# PMOD_STMod_connector.net
KiCad netlist of a schematic drawn in Altium Designer
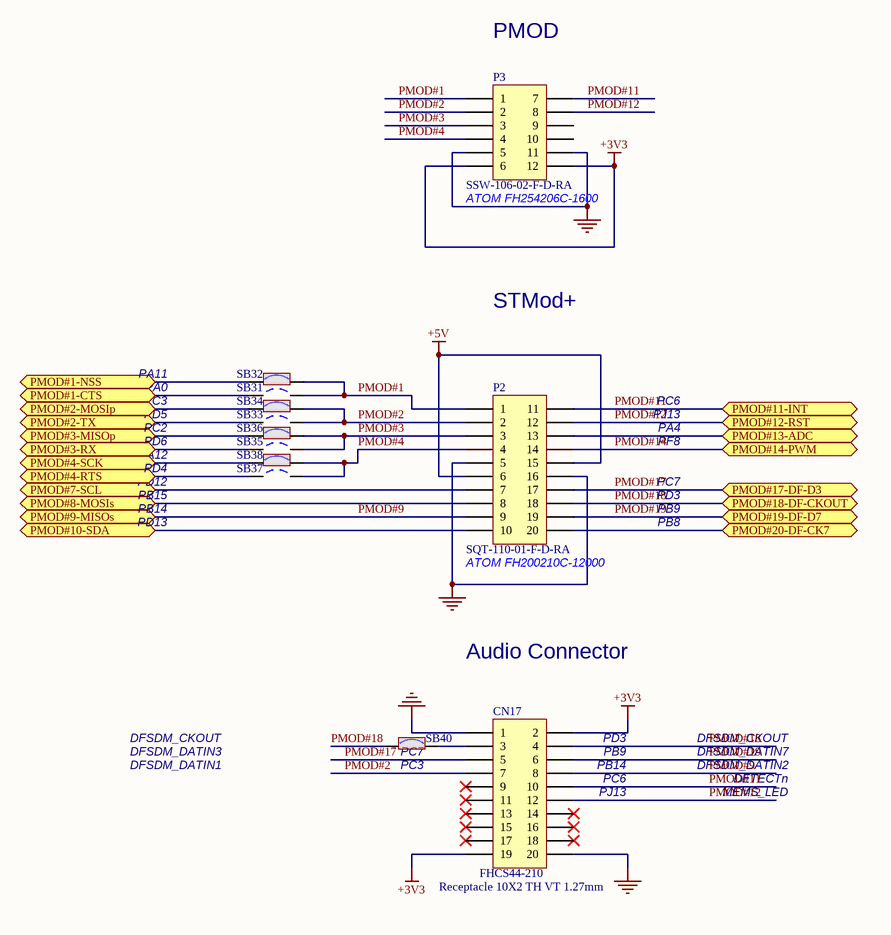
[diagram p0: PMOD_STMod+ connector .SchDoc]

(export (version "E")
  (design (tool "Eeschema 10.0.6"))
  (components
    (comp (ref "CN17")
      (value "Receptacle 10X2 TH VT 1.27mm")
      (footprint "MODULE_20TH_48X29")
      (description "20 Position Receptacle Connector 0.050\" (1.27mm) Through Hole Vertical Mount")
      (fields (field (name "ORDER_CODE") "FHCS44-210"))
      (libsource (lib "MCD_TEMP_PCH") (part "Receptacle 10X2 TH VT 1.27mm"))
    )
    (comp (ref "P2")
      (value "SQT-110-01-F-D-RA")
      (footprint "SQT-110-01-F-D-RA")
      (description "Header, 10-Pin, Dual row")
      (fields (field (name "PUBLISHER") "Altium Limited"))
      (libsource (lib "Miscellaneous Connectors") (part "Header 10X2A"))
    )
    (comp (ref "P3")
      (value "SSW-106-02-F-D-RA")
      (footprint "SSW-106-02-F-D-RA")
      (description "Header, 6-Pin, Dual row")
      (fields (field (name "PUBLISHER") "Altium Limited"))
      (libsource (lib "Miscellaneous Connectors") (part "Header 6X2A"))
    )
    (comp (ref "SB31")
      (value "Solder Bridge OFF")
      (footprint "SB_0603")
      (libsource (lib "MCD_TOOLS") (part "SB_OFF"))
    )
    (comp (ref "SB32")
      (value "Solder Bridge ON")
      (footprint "SB_0603")
      (libsource (lib "MCD_TOOLS") (part "SB_ON"))
    )
    (comp (ref "SB33")
      (value "Solder Bridge OFF")
      (footprint "SB_0603")
      (libsource (lib "MCD_TOOLS") (part "SB_OFF"))
    )
    (comp (ref "SB34")
      (value "Solder Bridge ON")
      (footprint "SB_0603")
      (libsource (lib "MCD_TOOLS") (part "SB_ON"))
    )
    (comp (ref "SB35")
      (value "Solder Bridge OFF")
      (footprint "SB_0603")
      (libsource (lib "MCD_TOOLS") (part "SB_OFF"))
    )
    (comp (ref "SB36")
      (value "Solder Bridge ON")
      (footprint "SB_0603")
      (libsource (lib "MCD_TOOLS") (part "SB_ON"))
    )
    (comp (ref "SB37")
      (value "Solder Bridge OFF")
      (footprint "SB_0603")
      (libsource (lib "MCD_TOOLS") (part "SB_OFF"))
    )
    (comp (ref "SB38")
      (value "Solder Bridge ON")
      (footprint "SB_0603")
      (libsource (lib "MCD_TOOLS") (part "SB_ON"))
    )
    (comp (ref "SB40")
      (value "Solder Bridge ON")
      (footprint "SB_0603")
      (libsource (lib "MCD_TOOLS") (part "SB_ON"))
    )
  )
  (nets
    (net (code "1") (name "+3V3") (class "Default")
      (node (ref "CN17") (pin "19") (pinfunction "19_19") (pintype "passive"))
      (node (ref "CN17") (pin "2") (pinfunction "2_2") (pintype "passive"))
      (node (ref "P3") (pin "12") (pinfunction "12_12") (pintype "passive"))
      (node (ref "P3") (pin "6") (pinfunction "6_6") (pintype "passive"))
    )
    (net (code "2") (name "+5V") (class "Default")
      (node (ref "P2") (pin "15") (pinfunction "15_15") (pintype "passive"))
      (node (ref "P2") (pin "6") (pinfunction "6_6") (pintype "passive"))
    )
    (net (code "3") (name "/PMOD#1") (class "Default")
      (node (ref "P2") (pin "1") (pinfunction "1_1") (pintype "passive"))
      (node (ref "P3") (pin "1") (pinfunction "1_1") (pintype "passive"))
      (node (ref "SB31") (pin "2") (pinfunction "2_2") (pintype "passive"))
      (node (ref "SB32") (pin "2") (pinfunction "2_2") (pintype "passive"))
    )
    (net (code "4") (name "/PMOD#1-CTS") (class "Default")
      (node (ref "SB31") (pin "1") (pinfunction "1_1") (pintype "passive"))
    )
    (net (code "5") (name "/PMOD#1-NSS") (class "Default")
      (node (ref "SB32") (pin "1") (pinfunction "1_1") (pintype "passive"))
    )
    (net (code "6") (name "/PMOD#2") (class "Default")
      (node (ref "CN17") (pin "7") (pinfunction "7_7") (pintype "passive"))
      (node (ref "P2") (pin "2") (pinfunction "2_2") (pintype "passive"))
      (node (ref "P3") (pin "2") (pinfunction "2_2") (pintype "passive"))
      (node (ref "SB33") (pin "2") (pinfunction "2_2") (pintype "passive"))
      (node (ref "SB34") (pin "2") (pinfunction "2_2") (pintype "passive"))
    )
    (net (code "7") (name "/PMOD#2-MOSIp") (class "Default")
      (node (ref "SB34") (pin "1") (pinfunction "1_1") (pintype "passive"))
    )
    (net (code "8") (name "/PMOD#2-TX") (class "Default")
      (node (ref "SB33") (pin "1") (pinfunction "1_1") (pintype "passive"))
    )
    (net (code "9") (name "/PMOD#3") (class "Default")
      (node (ref "P2") (pin "3") (pinfunction "3_3") (pintype "passive"))
      (node (ref "P3") (pin "3") (pinfunction "3_3") (pintype "passive"))
      (node (ref "SB35") (pin "2") (pinfunction "2_2") (pintype "passive"))
      (node (ref "SB36") (pin "2") (pinfunction "2_2") (pintype "passive"))
    )
    (net (code "10") (name "/PMOD#3-MISOp") (class "Default")
      (node (ref "SB36") (pin "1") (pinfunction "1_1") (pintype "passive"))
    )
    (net (code "11") (name "/PMOD#3-RX") (class "Default")
      (node (ref "SB35") (pin "1") (pinfunction "1_1") (pintype "passive"))
    )
    (net (code "12") (name "/PMOD#4") (class "Default")
      (node (ref "P2") (pin "4") (pinfunction "4_4") (pintype "passive"))
      (node (ref "P3") (pin "4") (pinfunction "4_4") (pintype "passive"))
      (node (ref "SB37") (pin "2") (pinfunction "2_2") (pintype "passive"))
      (node (ref "SB38") (pin "2") (pinfunction "2_2") (pintype "passive"))
    )
    (net (code "13") (name "/PMOD#4-RTS") (class "Default")
      (node (ref "SB37") (pin "1") (pinfunction "1_1") (pintype "passive"))
    )
    (net (code "14") (name "/PMOD#4-SCK") (class "Default")
      (node (ref "SB38") (pin "1") (pinfunction "1_1") (pintype "passive"))
    )
    (net (code "15") (name "/PMOD#7-SCL") (class "Default")
      (node (ref "P2") (pin "7") (pinfunction "7_7") (pintype "passive"))
    )
    (net (code "16") (name "/PMOD#8-MOSIs") (class "Default")
      (node (ref "P2") (pin "8") (pinfunction "8_8") (pintype "passive"))
    )
    (net (code "17") (name "/PMOD#9") (class "Default")
      (node (ref "CN17") (pin "8") (pinfunction "8_8") (pintype "passive"))
      (node (ref "P2") (pin "9") (pinfunction "9_9") (pintype "passive"))
    )
    (net (code "18") (name "/PMOD#10-SDA") (class "Default")
      (node (ref "P2") (pin "10") (pinfunction "10_10") (pintype "passive"))
    )
    (net (code "19") (name "/PMOD#11") (class "Default")
      (node (ref "CN17") (pin "10") (pinfunction "10_10") (pintype "passive"))
      (node (ref "P2") (pin "11") (pinfunction "11_11") (pintype "passive"))
      (node (ref "P3") (pin "7") (pinfunction "7_7") (pintype "passive"))
    )
    (net (code "20") (name "/PMOD#12") (class "Default")
      (node (ref "CN17") (pin "12") (pinfunction "12_12") (pintype "passive"))
      (node (ref "P2") (pin "12") (pinfunction "12_12") (pintype "passive"))
      (node (ref "P3") (pin "8") (pinfunction "8_8") (pintype "passive"))
    )
    (net (code "21") (name "/PMOD#13-ADC") (class "Default")
      (node (ref "P2") (pin "13") (pinfunction "13_13") (pintype "passive"))
    )
    (net (code "22") (name "/PMOD#14") (class "Default")
      (node (ref "P2") (pin "14") (pinfunction "14_14") (pintype "passive"))
    )
    (net (code "23") (name "/PMOD#17") (class "Default")
      (node (ref "CN17") (pin "5") (pinfunction "5_5") (pintype "passive"))
      (node (ref "P2") (pin "17") (pinfunction "17_17") (pintype "passive"))
    )
    (net (code "24") (name "/PMOD#18") (class "Default")
      (node (ref "CN17") (pin "4") (pinfunction "4_4") (pintype "passive"))
      (node (ref "P2") (pin "18") (pinfunction "18_18") (pintype "passive"))
      (node (ref "SB40") (pin "1") (pinfunction "1_1") (pintype "passive"))
    )
    (net (code "25") (name "/PMOD#19") (class "Default")
      (node (ref "CN17") (pin "6") (pinfunction "6_6") (pintype "passive"))
      (node (ref "P2") (pin "19") (pinfunction "19_19") (pintype "passive"))
    )
    (net (code "26") (name "/PMOD#20-DF-CK7") (class "Default")
      (node (ref "P2") (pin "20") (pinfunction "20_20") (pintype "passive"))
    )
    (net (code "27") (name "GND") (class "Default")
      (node (ref "CN17") (pin "1") (pinfunction "1_1") (pintype "passive"))
      (node (ref "CN17") (pin "20") (pinfunction "20_20") (pintype "passive"))
      (node (ref "P2") (pin "16") (pinfunction "16_16") (pintype "passive"))
      (node (ref "P2") (pin "5") (pinfunction "5_5") (pintype "passive"))
      (node (ref "P3") (pin "11") (pinfunction "11_11") (pintype "passive"))
      (node (ref "P3") (pin "5") (pinfunction "5_5") (pintype "passive"))
    )
    (net (code "28") (name "Net-(CN17-Pad3)") (class "Default")
      (node (ref "CN17") (pin "3") (pinfunction "3_3") (pintype "passive"))
      (node (ref "SB40") (pin "2") (pinfunction "2_2") (pintype "passive"))
    )
    (net (code "29") (name "unconnected-(CN17-Pad9)") (class "Default")
      (node (ref "CN17") (pin "9") (pinfunction "9_9") (pintype "passive+no_connect"))
    )
    (net (code "30") (name "unconnected-(CN17-Pad11)") (class "Default")
      (node (ref "CN17") (pin "11") (pinfunction "11_11") (pintype "passive+no_connect"))
    )
    (net (code "31") (name "unconnected-(CN17-Pad13)") (class "Default")
      (node (ref "CN17") (pin "13") (pinfunction "13_13") (pintype "passive+no_connect"))
    )
    (net (code "32") (name "unconnected-(CN17-Pad14)") (class "Default")
      (node (ref "CN17") (pin "14") (pinfunction "14_14") (pintype "passive+no_connect"))
    )
    (net (code "33") (name "unconnected-(CN17-Pad15)") (class "Default")
      (node (ref "CN17") (pin "15") (pinfunction "15_15") (pintype "passive+no_connect"))
    )
    (net (code "34") (name "unconnected-(CN17-Pad16)") (class "Default")
      (node (ref "CN17") (pin "16") (pinfunction "16_16") (pintype "passive+no_connect"))
    )
    (net (code "35") (name "unconnected-(CN17-Pad17)") (class "Default")
      (node (ref "CN17") (pin "17") (pinfunction "17_17") (pintype "passive+no_connect"))
    )
    (net (code "36") (name "unconnected-(CN17-Pad18)") (class "Default")
      (node (ref "CN17") (pin "18") (pinfunction "18_18") (pintype "passive+no_connect"))
    )
    (net (code "37") (name "unconnected-(P3-Pad9)") (class "Default")
      (node (ref "P3") (pin "9") (pinfunction "9_9") (pintype "passive"))
    )
    (net (code "38") (name "unconnected-(P3-Pad10)") (class "Default")
      (node (ref "P3") (pin "10") (pinfunction "10_10") (pintype "passive"))
    )
  )
)
